# ui_qspi.net
KiCad netlist of a schematic drawn in Altium Designer
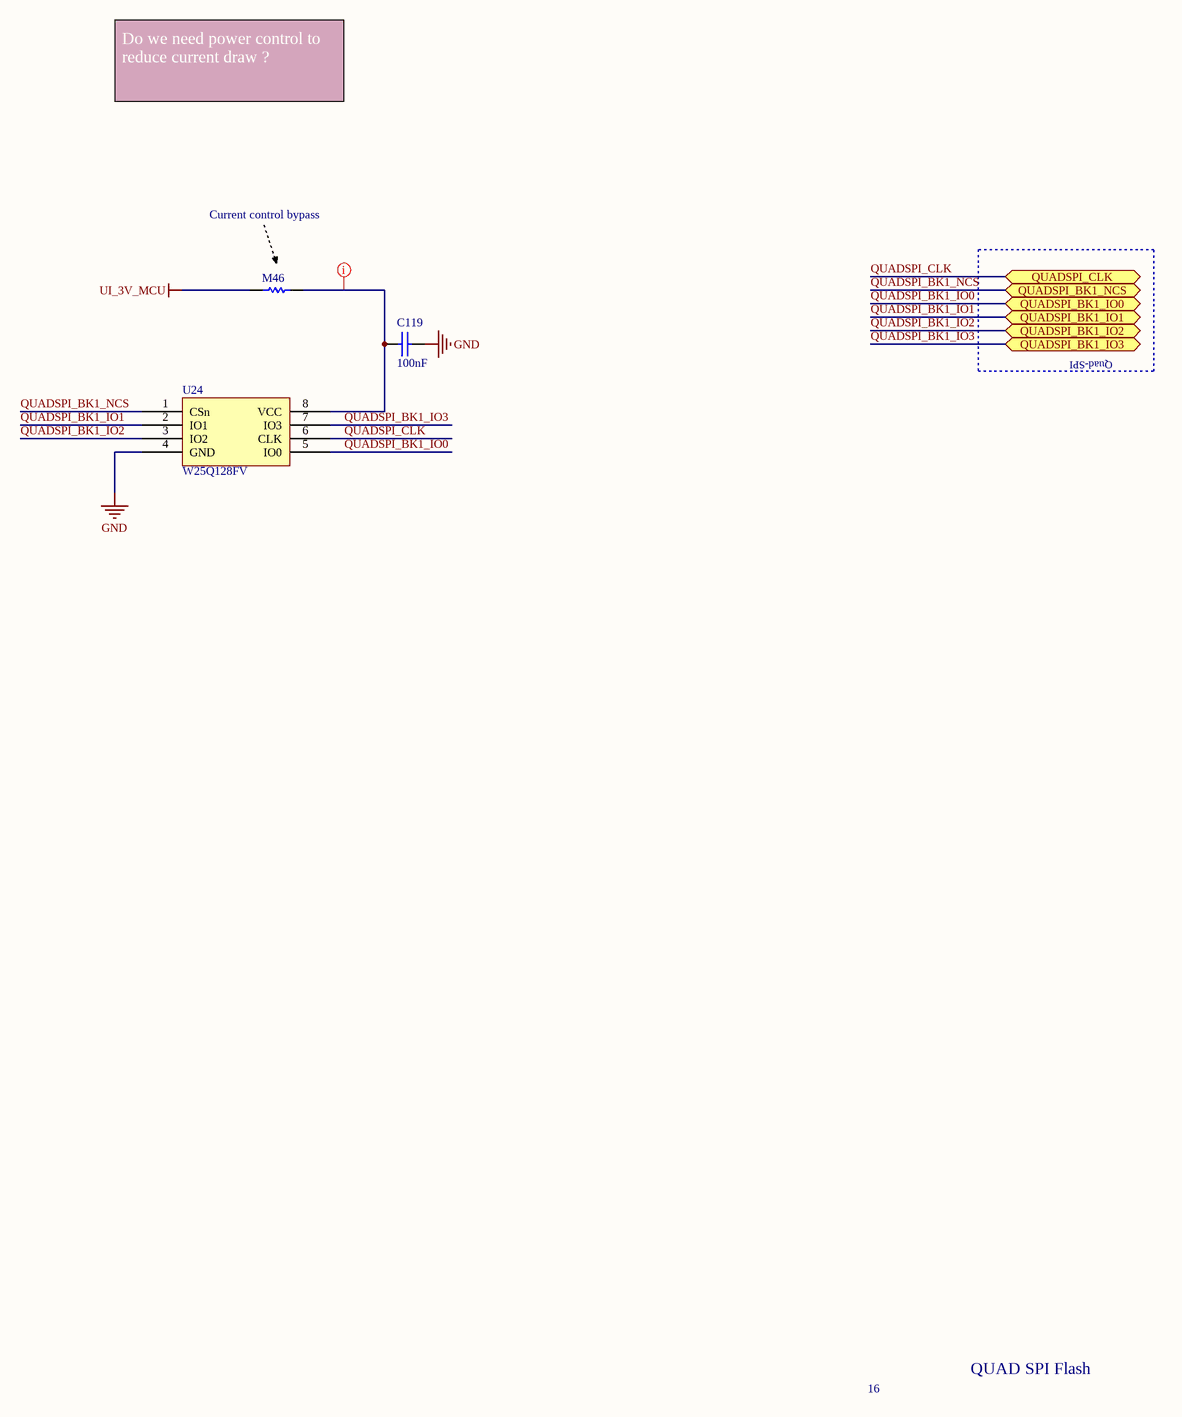
[diagram p0: ui_qspi.SchDoc]

(export (version "E")
  (design (tool "Eeschema 10.0.6"))
  (components
    (comp (ref "C119")
      (value "100nF")
      (footprint "0805")
      (description "Capacitor")
      (libsource (lib "mcHF_ui") (part "CAP"))
    )
    (comp (ref "M46")
      (value "0")
      (footprint "SB_0603")
      (description "Link")
      (fields (field (name "PUBLISHER") "Altium Limited"))
      (libsource (lib "__ui") (part "Link"))
    )
    (comp (ref "U24")
      (value "W25Q128FV")
      (footprint "SOIC8_208MIL")
      (description "3V 128Mbit QUAD SPI")
      (libsource (lib "__ui") (part "W25Q128FV"))
    )
  )
  (nets
    (net (code "1") (name "/QUADSPI_BK1_IO0") (class "Default")
      (node (ref "U24") (pin "5") (pinfunction "IO0_5") (pintype "passive"))
    )
    (net (code "2") (name "/QUADSPI_BK1_IO1") (class "Default")
      (node (ref "U24") (pin "2") (pinfunction "IO1_2") (pintype "passive"))
    )
    (net (code "3") (name "/QUADSPI_BK1_IO2") (class "Default")
      (node (ref "U24") (pin "3") (pinfunction "IO2_3") (pintype "passive"))
    )
    (net (code "4") (name "/QUADSPI_BK1_IO3") (class "Default")
      (node (ref "U24") (pin "7") (pinfunction "IO3_7") (pintype "passive"))
    )
    (net (code "5") (name "/QUADSPI_BK1_NCS") (class "Default")
      (node (ref "U24") (pin "1") (pinfunction "CSn_1") (pintype "passive"))
    )
    (net (code "6") (name "/QUADSPI_CLK") (class "Default")
      (node (ref "U24") (pin "6") (pinfunction "CLK_6") (pintype "passive"))
    )
    (net (code "7") (name "GND") (class "Default")
      (node (ref "C119") (pin "2") (pinfunction "2_2") (pintype "passive"))
      (node (ref "U24") (pin "4") (pinfunction "GND_4") (pintype "passive"))
    )
    (net (code "8") (name "Net-(U24-VCC)") (class "Default")
      (node (ref "C119") (pin "1") (pinfunction "1_1") (pintype "passive"))
      (node (ref "M46") (pin "2") (pinfunction "2_2") (pintype "passive"))
      (node (ref "U24") (pin "8") (pinfunction "VCC_8") (pintype "passive"))
    )
    (net (code "9") (name "UI_3V_MCU") (class "Default")
      (node (ref "M46") (pin "1") (pinfunction "1_1") (pintype "passive"))
    )
  )
)
